# IotaWatt5_0.net
KiCad netlist of a schematic drawn in EAGLE
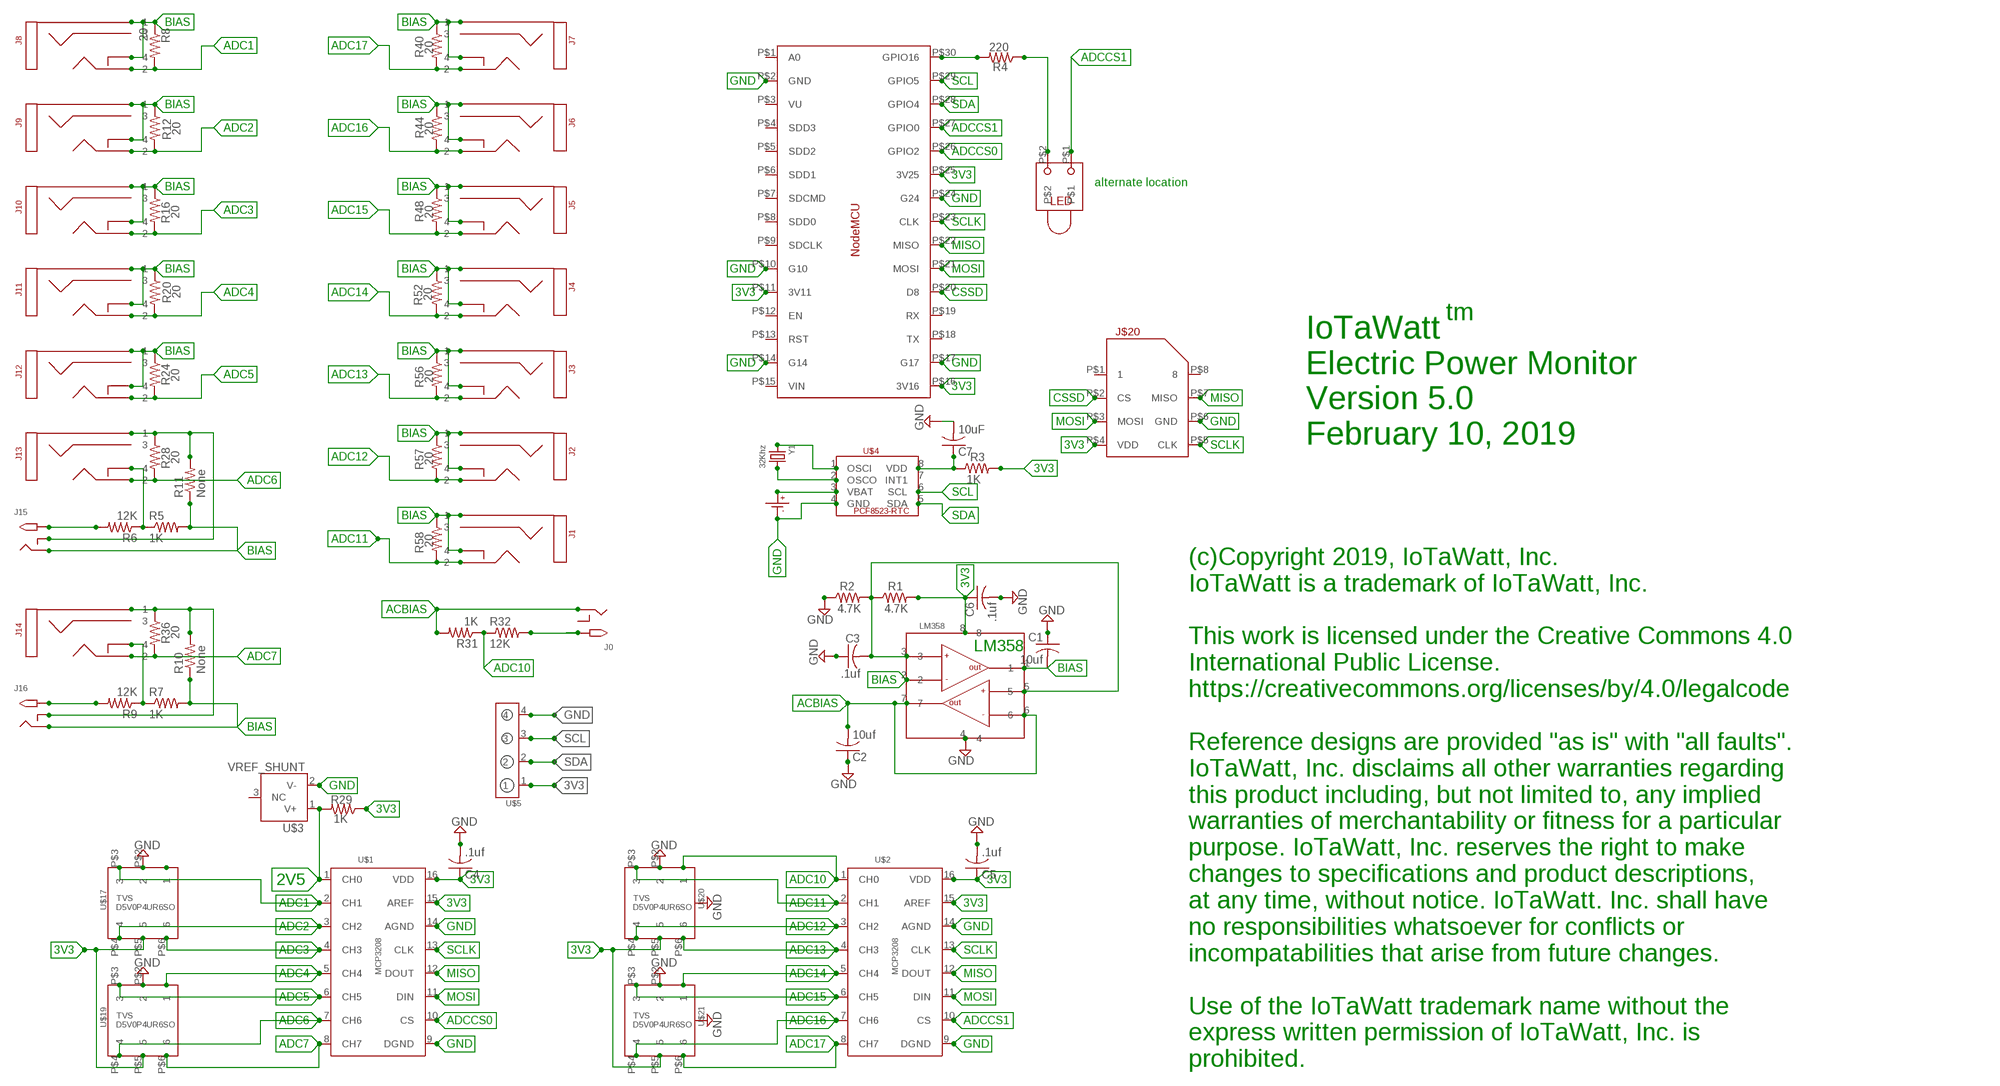
[diagram p0: schematic, sheet 1]

(export (version "E")
  (design (tool "Eeschema 10.0.6"))
  (components
    (comp (ref "C1")
      (value "10uf")
      (footprint "eagle-import:C0805")
      (fields (field (name "LCSC_PART") "C15850"))
      (libsource (lib "eagle-import") (part "C-USC0805"))
    )
    (comp (ref "C2")
      (value "10uf")
      (footprint "eagle-import:C0805")
      (fields (field (name "LCSC_PART") "C15850"))
      (libsource (lib "eagle-import") (part "C-USC0805"))
    )
    (comp (ref "C3")
      (value ".1uf")
      (footprint "eagle-import:C0805")
      (fields (field (name "LCSC_PART") "C49678"))
      (libsource (lib "eagle-import") (part "C-USC0805"))
    )
    (comp (ref "C4")
      (value ".1uf")
      (footprint "eagle-import:C0805")
      (fields (field (name "LCSC_PART") "C49678"))
      (libsource (lib "eagle-import") (part "C-USC0805"))
    )
    (comp (ref "C5")
      (value ".1uf")
      (footprint "eagle-import:C0805")
      (fields (field (name "LCSC_PART") "C49678"))
      (libsource (lib "eagle-import") (part "C-USC0805"))
    )
    (comp (ref "C6")
      (value ".1uf")
      (footprint "eagle-import:C0805")
      (fields (field (name "LCSC_PART") "C49678"))
      (libsource (lib "eagle-import") (part "C-USC0805"))
    )
    (comp (ref "C7")
      (value "10uF")
      (footprint "eagle-import:C0805")
      (fields (field (name "LCSC_PART") "C15850"))
      (libsource (lib "eagle-import") (part "C-USC0805"))
    )
    (comp (ref "J$20")
      (value "MICROSD_PUSH/PULL")
      (footprint "eagle-import:MICROSD")
      (libsource (lib "eagle-import") (part "MICROSD_PUSH/PULL"))
    )
    (comp (ref "J0")
      (value "2.1MMJACKSMT")
      (footprint "eagle-import:DCJACK_2MM_SMT")
      (libsource (lib "eagle-import") (part "2.1MMJACKSMT"))
    )
    (comp (ref "J1")
      (value "STEREO_SMD")
      (footprint "eagle-import:STEREO_SMT")
      (libsource (lib "eagle-import") (part "STEREO_SMD"))
    )
    (comp (ref "J2")
      (value "STEREO_SMD")
      (footprint "eagle-import:STEREO_SMT")
      (libsource (lib "eagle-import") (part "STEREO_SMD"))
    )
    (comp (ref "J3")
      (value "STEREO_SMD")
      (footprint "eagle-import:STEREO_SMT")
      (libsource (lib "eagle-import") (part "STEREO_SMD"))
    )
    (comp (ref "J4")
      (value "STEREO_SMD")
      (footprint "eagle-import:STEREO_SMT")
      (libsource (lib "eagle-import") (part "STEREO_SMD"))
    )
    (comp (ref "J5")
      (value "STEREO_SMD")
      (footprint "eagle-import:STEREO_SMT")
      (libsource (lib "eagle-import") (part "STEREO_SMD"))
    )
    (comp (ref "J6")
      (value "STEREO_SMD")
      (footprint "eagle-import:STEREO_SMT")
      (libsource (lib "eagle-import") (part "STEREO_SMD"))
    )
    (comp (ref "J7")
      (value "STEREO_SMD")
      (footprint "eagle-import:STEREO_SMT")
      (libsource (lib "eagle-import") (part "STEREO_SMD"))
    )
    (comp (ref "J8")
      (value "STEREO_SMD")
      (footprint "eagle-import:STEREO_SMT")
      (libsource (lib "eagle-import") (part "STEREO_SMD"))
    )
    (comp (ref "J9")
      (value "STEREO_SMD")
      (footprint "eagle-import:STEREO_SMT")
      (libsource (lib "eagle-import") (part "STEREO_SMD"))
    )
    (comp (ref "J10")
      (value "STEREO_SMD")
      (footprint "eagle-import:STEREO_SMT")
      (libsource (lib "eagle-import") (part "STEREO_SMD"))
    )
    (comp (ref "J11")
      (value "STEREO_SMD")
      (footprint "eagle-import:STEREO_SMT")
      (libsource (lib "eagle-import") (part "STEREO_SMD"))
    )
    (comp (ref "J12")
      (value "STEREO_SMD")
      (footprint "eagle-import:STEREO_SMT")
      (libsource (lib "eagle-import") (part "STEREO_SMD"))
    )
    (comp (ref "J13")
      (value "STEREO_SMD")
      (footprint "eagle-import:STEREO_SMT")
      (libsource (lib "eagle-import") (part "STEREO_SMD"))
    )
    (comp (ref "J14")
      (value "STEREO_SMD")
      (footprint "eagle-import:STEREO_SMT")
      (libsource (lib "eagle-import") (part "STEREO_SMD"))
    )
    (comp (ref "J15")
      (value "2.1MMJACKSMT")
      (footprint "eagle-import:DCJACK_2MM_SMT")
      (libsource (lib "eagle-import") (part "2.1MMJACKSMT"))
    )
    (comp (ref "J16")
      (value "2.1MMJACKSMT")
      (footprint "eagle-import:DCJACK_2MM_SMT")
      (libsource (lib "eagle-import") (part "2.1MMJACKSMT"))
    )
    (comp (ref "R1")
      (value "4.7K")
      (footprint "eagle-import:R0805")
      (fields (field (name "LCSC_PART") "C515732"))
      (libsource (lib "eagle-import") (part "R-US_R0805"))
    )
    (comp (ref "R2")
      (value "4.7K")
      (footprint "eagle-import:R0805")
      (fields (field (name "LCSC_PART") "C515732"))
      (libsource (lib "eagle-import") (part "R-US_R0805"))
    )
    (comp (ref "R3")
      (value "1K")
      (footprint "eagle-import:R0805")
      (fields (field (name "LCSC_PART") "C309081"))
      (libsource (lib "eagle-import") (part "R-US_R0805"))
    )
    (comp (ref "R4")
      (value "220")
      (footprint "eagle-import:R0805")
      (fields (field (name "LCSC_PART") "C17557"))
      (libsource (lib "eagle-import") (part "R-US_R0805"))
    )
    (comp (ref "R5")
      (value "1K")
      (footprint "eagle-import:R0805")
      (fields (field (name "LCSC_PART") "C309081"))
      (libsource (lib "eagle-import") (part "R-US_R0805"))
    )
    (comp (ref "R6")
      (value "12K")
      (footprint "eagle-import:R0805")
      (fields (field (name "LCSC_PART") "C515719"))
      (libsource (lib "eagle-import") (part "R-US_R0805"))
    )
    (comp (ref "R7")
      (value "1K")
      (footprint "eagle-import:R0805")
      (fields (field (name "LCSC_PART") "C309081"))
      (libsource (lib "eagle-import") (part "R-US_R0805"))
    )
    (comp (ref "R8")
      (value "20")
      (footprint "eagle-import:R0805")
      (fields (field (name "LCSC_PART") "C723660"))
      (libsource (lib "eagle-import") (part "R-US_R0805"))
    )
    (comp (ref "R9")
      (value "12K")
      (footprint "eagle-import:R0805")
      (fields (field (name "LCSC_PART") "C515719"))
      (libsource (lib "eagle-import") (part "R-US_R0805"))
    )
    (comp (ref "R10")
      (value "None")
      (footprint "eagle-import:R0805")
      (fields (field (name "LCSC_PART") "C17477"))
      (libsource (lib "eagle-import") (part "R-US_R0805"))
    )
    (comp (ref "R11")
      (value "None")
      (footprint "eagle-import:R0805")
      (fields (field (name "LCSC_PART") "C17477"))
      (libsource (lib "eagle-import") (part "R-US_R0805"))
    )
    (comp (ref "R12")
      (value "20")
      (footprint "eagle-import:R0805")
      (fields (field (name "LCSC_PART") "C723660"))
      (libsource (lib "eagle-import") (part "R-US_R0805"))
    )
    (comp (ref "R16")
      (value "20")
      (footprint "eagle-import:R0805")
      (fields (field (name "LCSC_PART") "C723660"))
      (libsource (lib "eagle-import") (part "R-US_R0805"))
    )
    (comp (ref "R20")
      (value "20")
      (footprint "eagle-import:R0805")
      (fields (field (name "LCSC_PART") "C723660"))
      (libsource (lib "eagle-import") (part "R-US_R0805"))
    )
    (comp (ref "R24")
      (value "20")
      (footprint "eagle-import:R0805")
      (fields (field (name "LCSC_PART") "C723660"))
      (libsource (lib "eagle-import") (part "R-US_R0805"))
    )
    (comp (ref "R28")
      (value "20")
      (footprint "eagle-import:R0805")
      (fields (field (name "LCSC_PART") "C723660"))
      (libsource (lib "eagle-import") (part "R-US_R0805"))
    )
    (comp (ref "R29")
      (value "1K")
      (footprint "eagle-import:R0805")
      (fields (field (name "LCSC_PART") "C309081"))
      (libsource (lib "eagle-import") (part "R-US_R0805"))
    )
    (comp (ref "R31")
      (value "1K")
      (footprint "eagle-import:R0805")
      (fields (field (name "LCSC_PART") "C309081"))
      (libsource (lib "eagle-import") (part "R-US_R0805"))
    )
    (comp (ref "R32")
      (value "12K")
      (footprint "eagle-import:R0805")
      (fields (field (name "LCSC_PART") "C515719"))
      (libsource (lib "eagle-import") (part "R-US_R0805"))
    )
    (comp (ref "R36")
      (value "20")
      (footprint "eagle-import:R0805")
      (fields (field (name "LCSC_PART") "C723660"))
      (libsource (lib "eagle-import") (part "R-US_R0805"))
    )
    (comp (ref "R40")
      (value "20")
      (footprint "eagle-import:R0805")
      (fields (field (name "LCSC_PART") "C723660"))
      (libsource (lib "eagle-import") (part "R-US_R0805"))
    )
    (comp (ref "R44")
      (value "20")
      (footprint "eagle-import:R0805")
      (fields (field (name "LCSC_PART") "C723660"))
      (libsource (lib "eagle-import") (part "R-US_R0805"))
    )
    (comp (ref "R48")
      (value "20")
      (footprint "eagle-import:R0805")
      (fields (field (name "LCSC_PART") "C723660"))
      (libsource (lib "eagle-import") (part "R-US_R0805"))
    )
    (comp (ref "R52")
      (value "20")
      (footprint "eagle-import:R0805")
      (fields (field (name "LCSC_PART") "C723660"))
      (libsource (lib "eagle-import") (part "R-US_R0805"))
    )
    (comp (ref "R56")
      (value "20")
      (footprint "eagle-import:R0805")
      (fields (field (name "LCSC_PART") "C723660"))
      (libsource (lib "eagle-import") (part "R-US_R0805"))
    )
    (comp (ref "R57")
      (value "20")
      (footprint "eagle-import:R0805")
      (fields (field (name "LCSC_PART") "C723660"))
      (libsource (lib "eagle-import") (part "R-US_R0805"))
    )
    (comp (ref "R58")
      (value "20")
      (footprint "eagle-import:R0805")
      (fields (field (name "LCSC_PART") "C723660"))
      (libsource (lib "eagle-import") (part "R-US_R0805"))
    )
    (comp (ref "U$1")
      (value "MCP3208")
      (footprint "eagle-import:SOIC_16")
      (fields (field (name "LCSC_PART") "C16939"))
      (libsource (lib "eagle-import") (part "MCP3208"))
    )
    (comp (ref "U$2")
      (value "MCP3208")
      (footprint "eagle-import:SOIC_16")
      (fields (field (name "LCSC_PART") "C16939"))
      (libsource (lib "eagle-import") (part "MCP3208"))
    )
    (comp (ref "U$3")
      (value "VREF_SHUNT")
      (footprint "eagle-import:SOT23_3")
      (libsource (lib "eagle-import") (part "VREF_SHUNT"))
    )
    (comp (ref "U$4")
      (value "PCF8523_RTC")
      (footprint "eagle-import:SOIC_8")
      (fields (field (name "LCSC_PART") "C2651516"))
      (libsource (lib "eagle-import") (part "PCF8523_RTC"))
    )
    (comp (ref "U$5")
      (value "HEADER_1X4")
      (footprint "eagle-import:HEADER_1X4")
      (libsource (lib "eagle-import") (part "HEADER_1X4"))
    )
    (comp (ref "U$16")
      (value "NODEMCU")
      (footprint "eagle-import:NODEMCU")
      (libsource (lib "eagle-import") (part "NODEMCU"))
    )
    (comp (ref "U$17")
      (value "TVS_4CHAN_ARRAYSC-74")
      (footprint "eagle-import:SC-74")
      (fields (field (name "LCSC_PART") "C531179"))
      (libsource (lib "eagle-import") (part "TVS_4CHAN_ARRAYSC-74"))
    )
    (comp (ref "U$18")
      (value "CR1220SMD")
      (footprint "eagle-import:CR1220SMD")
      (libsource (lib "eagle-import") (part "CR1220SMD"))
    )
    (comp (ref "U$19")
      (value "TVS_4CHAN_ARRAYSC-74")
      (footprint "eagle-import:SC-74")
      (fields (field (name "LCSC_PART") "C531179"))
      (libsource (lib "eagle-import") (part "TVS_4CHAN_ARRAYSC-74"))
    )
    (comp (ref "U$20")
      (value "TVS_4CHAN_ARRAYSC-74")
      (footprint "eagle-import:SC-74")
      (fields (field (name "LCSC_PART") "C531179"))
      (libsource (lib "eagle-import") (part "TVS_4CHAN_ARRAYSC-74"))
    )
    (comp (ref "U$21")
      (value "TVS_4CHAN_ARRAYSC-74")
      (footprint "eagle-import:SC-74")
      (fields (field (name "LCSC_PART") "C531179"))
      (libsource (lib "eagle-import") (part "TVS_4CHAN_ARRAYSC-74"))
    )
    (comp (ref "U$22")
      (value "LM358_DUAL_OP-AMP")
      (footprint "eagle-import:SOIC_8")
      (fields (field (name "LCSC_PART") "C5423"))
      (libsource (lib "eagle-import") (part "LM358_DUAL_OP-AMP"))
    )
    (comp (ref "U$23")
      (value "LED_RT_TRH")
      (footprint "eagle-import:LED_TH_RT")
      (libsource (lib "eagle-import") (part "LED_RT_TRH"))
    )
    (comp (ref "Y1")
      (value "32Khz")
      (footprint "eagle-import:CRYSTAL_8X3.8")
      (fields (field (name "LCSC_PART") "C179637"))
      (libsource (lib "eagle-import") (part "CRYSTAL8X3.8SMT"))
    )
  )
  (nets
    (net (code "1") (name "2V5") (class "Default")
      (node (ref "R29") (pin "2") (pinfunction "2_2") (pintype "passive"))
      (node (ref "U$1") (pin "1") (pinfunction "CH0_1") (pintype "input"))
      (node (ref "U$3") (pin "1") (pinfunction "V+_1") (pintype "bidirectional"))
    )
    (net (code "2") (name "3V3") (class "Default")
      (node (ref "C4") (pin "1") (pinfunction "1_1") (pintype "passive"))
      (node (ref "C5") (pin "1") (pinfunction "1_1") (pintype "passive"))
      (node (ref "C6") (pin "1") (pinfunction "1_1") (pintype "passive"))
      (node (ref "J$20") (pin "P$4") (pinfunction "VDD_P$4") (pintype "bidirectional"))
      (node (ref "R1") (pin "2") (pinfunction "2_2") (pintype "passive"))
      (node (ref "R29") (pin "1") (pinfunction "1_1") (pintype "passive"))
      (node (ref "R3") (pin "2") (pinfunction "2_2") (pintype "passive"))
      (node (ref "U$1") (pin "15") (pinfunction "AREF_15") (pintype "input"))
      (node (ref "U$1") (pin "16") (pinfunction "VDD_16") (pintype "bidirectional"))
      (node (ref "U$16") (pin "P$11") (pinfunction "3V11_P$11") (pintype "bidirectional"))
      (node (ref "U$16") (pin "P$16") (pinfunction "3V16_P$16") (pintype "bidirectional"))
      (node (ref "U$16") (pin "P$25") (pinfunction "3V25_P$25") (pintype "bidirectional"))
      (node (ref "U$17") (pin "P$5") (pinfunction "5_P$5") (pintype "bidirectional"))
      (node (ref "U$19") (pin "P$5") (pinfunction "5_P$5") (pintype "bidirectional"))
      (node (ref "U$2") (pin "15") (pinfunction "AREF_15") (pintype "input"))
      (node (ref "U$2") (pin "16") (pinfunction "VDD_16") (pintype "bidirectional"))
      (node (ref "U$20") (pin "P$5") (pinfunction "5_P$5") (pintype "bidirectional"))
      (node (ref "U$21") (pin "P$5") (pinfunction "5_P$5") (pintype "bidirectional"))
      (node (ref "U$22") (pin "8") (pinfunction "8_8") (pintype "bidirectional"))
      (node (ref "U$5") (pin "1") (pinfunction "1_1") (pintype "bidirectional"))
    )
    (net (code "3") (name "ACBIAS") (class "Default")
      (node (ref "C2") (pin "2") (pinfunction "2_2") (pintype "passive"))
      (node (ref "J0") (pin "GND") (pinfunction "RING_GND") (pintype "bidirectional"))
      (node (ref "R31") (pin "2") (pinfunction "2_2") (pintype "passive"))
      (node (ref "U$22") (pin "6") (pinfunction "6_6") (pintype "bidirectional"))
      (node (ref "U$22") (pin "7") (pinfunction "7_7") (pintype "bidirectional"))
    )
    (net (code "4") (name "ADC1") (class "Default")
      (node (ref "J8") (pin "P$2") (pinfunction "2_P$2") (pintype "bidirectional"))
      (node (ref "R8") (pin "2") (pinfunction "2_2") (pintype "passive"))
      (node (ref "U$1") (pin "2") (pinfunction "CH1_2") (pintype "input"))
      (node (ref "U$17") (pin "P$3") (pinfunction "3_P$3") (pintype "bidirectional"))
    )
    (net (code "5") (name "ADC2") (class "Default")
      (node (ref "J9") (pin "P$2") (pinfunction "2_P$2") (pintype "bidirectional"))
      (node (ref "R12") (pin "2") (pinfunction "2_2") (pintype "passive"))
      (node (ref "U$1") (pin "3") (pinfunction "CH2_3") (pintype "input"))
      (node (ref "U$17") (pin "P$4") (pinfunction "4_P$4") (pintype "bidirectional"))
    )
    (net (code "6") (name "ADC3") (class "Default")
      (node (ref "J10") (pin "P$2") (pinfunction "2_P$2") (pintype "bidirectional"))
      (node (ref "R16") (pin "2") (pinfunction "2_2") (pintype "passive"))
      (node (ref "U$1") (pin "4") (pinfunction "CH3_4") (pintype "input"))
      (node (ref "U$17") (pin "P$6") (pinfunction "6_P$6") (pintype "bidirectional"))
    )
    (net (code "7") (name "ADC4") (class "Default")
      (node (ref "J11") (pin "P$2") (pinfunction "2_P$2") (pintype "bidirectional"))
      (node (ref "R20") (pin "2") (pinfunction "2_2") (pintype "passive"))
      (node (ref "U$1") (pin "5") (pinfunction "CH4_5") (pintype "bidirectional"))
      (node (ref "U$19") (pin "P$1") (pinfunction "1_P$1") (pintype "bidirectional"))
    )
    (net (code "8") (name "ADC5") (class "Default")
      (node (ref "J12") (pin "P$2") (pinfunction "2_P$2") (pintype "bidirectional"))
      (node (ref "R24") (pin "2") (pinfunction "2_2") (pintype "passive"))
      (node (ref "U$1") (pin "6") (pinfunction "CH5_6") (pintype "bidirectional"))
      (node (ref "U$19") (pin "P$3") (pinfunction "3_P$3") (pintype "bidirectional"))
    )
    (net (code "9") (name "ADC6") (class "Default")
      (node (ref "J13") (pin "P$2") (pinfunction "2_P$2") (pintype "bidirectional"))
      (node (ref "R28") (pin "2") (pinfunction "2_2") (pintype "passive"))
      (node (ref "U$1") (pin "7") (pinfunction "CH6_7") (pintype "input"))
      (node (ref "U$19") (pin "P$4") (pinfunction "4_P$4") (pintype "bidirectional"))
    )
    (net (code "10") (name "ADC7") (class "Default")
      (node (ref "J14") (pin "P$2") (pinfunction "2_P$2") (pintype "bidirectional"))
      (node (ref "R36") (pin "2") (pinfunction "2_2") (pintype "passive"))
      (node (ref "U$1") (pin "8") (pinfunction "CH7_8") (pintype "bidirectional"))
      (node (ref "U$19") (pin "P$6") (pinfunction "6_P$6") (pintype "bidirectional"))
    )
    (net (code "11") (name "ADC10") (class "Default")
      (node (ref "R31") (pin "1") (pinfunction "1_1") (pintype "passive"))
      (node (ref "R32") (pin "1") (pinfunction "1_1") (pintype "passive"))
      (node (ref "U$2") (pin "1") (pinfunction "CH0_1") (pintype "input"))
      (node (ref "U$20") (pin "P$1") (pinfunction "1_P$1") (pintype "bidirectional"))
    )
    (net (code "12") (name "ADC11") (class "Default")
      (node (ref "J1") (pin "P$2") (pinfunction "2_P$2") (pintype "bidirectional"))
      (node (ref "R58") (pin "2") (pinfunction "2_2") (pintype "passive"))
      (node (ref "U$2") (pin "2") (pinfunction "CH1_2") (pintype "input"))
      (node (ref "U$20") (pin "P$3") (pinfunction "3_P$3") (pintype "bidirectional"))
    )
    (net (code "13") (name "ADC12") (class "Default")
      (node (ref "J2") (pin "P$2") (pinfunction "2_P$2") (pintype "bidirectional"))
      (node (ref "R57") (pin "2") (pinfunction "2_2") (pintype "passive"))
      (node (ref "U$2") (pin "3") (pinfunction "CH2_3") (pintype "input"))
      (node (ref "U$20") (pin "P$4") (pinfunction "4_P$4") (pintype "bidirectional"))
    )
    (net (code "14") (name "ADC13") (class "Default")
      (node (ref "J3") (pin "P$2") (pinfunction "2_P$2") (pintype "bidirectional"))
      (node (ref "R56") (pin "2") (pinfunction "2_2") (pintype "passive"))
      (node (ref "U$2") (pin "4") (pinfunction "CH3_4") (pintype "input"))
      (node (ref "U$20") (pin "P$6") (pinfunction "6_P$6") (pintype "bidirectional"))
    )
    (net (code "15") (name "ADC14") (class "Default")
      (node (ref "J4") (pin "P$2") (pinfunction "2_P$2") (pintype "bidirectional"))
      (node (ref "R52") (pin "2") (pinfunction "2_2") (pintype "passive"))
      (node (ref "U$2") (pin "5") (pinfunction "CH4_5") (pintype "bidirectional"))
      (node (ref "U$21") (pin "P$1") (pinfunction "1_P$1") (pintype "bidirectional"))
    )
    (net (code "16") (name "ADC15") (class "Default")
      (node (ref "J5") (pin "P$2") (pinfunction "2_P$2") (pintype "bidirectional"))
      (node (ref "R48") (pin "2") (pinfunction "2_2") (pintype "passive"))
      (node (ref "U$2") (pin "6") (pinfunction "CH5_6") (pintype "bidirectional"))
      (node (ref "U$21") (pin "P$3") (pinfunction "3_P$3") (pintype "bidirectional"))
    )
    (net (code "17") (name "ADC16") (class "Default")
      (node (ref "J6") (pin "P$2") (pinfunction "2_P$2") (pintype "bidirectional"))
      (node (ref "R44") (pin "2") (pinfunction "2_2") (pintype "passive"))
      (node (ref "U$2") (pin "7") (pinfunction "CH6_7") (pintype "input"))
      (node (ref "U$21") (pin "P$4") (pinfunction "4_P$4") (pintype "bidirectional"))
    )
    (net (code "18") (name "ADC17") (class "Default")
      (node (ref "J7") (pin "P$2") (pinfunction "2_P$2") (pintype "bidirectional"))
      (node (ref "R40") (pin "2") (pinfunction "2_2") (pintype "passive"))
      (node (ref "U$2") (pin "8") (pinfunction "CH7_8") (pintype "bidirectional"))
      (node (ref "U$21") (pin "P$6") (pinfunction "6_P$6") (pintype "bidirectional"))
    )
    (net (code "19") (name "ADCCS0") (class "Default")
      (node (ref "U$1") (pin "10") (pinfunction "CS_10") (pintype "input"))
      (node (ref "U$16") (pin "P$26") (pinfunction "GPIO2_P$26") (pintype "bidirectional"))
    )
    (net (code "20") (name "ADCCS1") (class "Default")
      (node (ref "U$16") (pin "P$27") (pinfunction "GPIO0_P$27") (pintype "bidirectional"))
      (node (ref "U$2") (pin "10") (pinfunction "CS_10") (pintype "input"))
      (node (ref "U$23") (pin "P$1") (pinfunction "P$1_P$1") (pintype "bidirectional"))
    )
    (net (code "21") (name "BIAS") (class "Default")
      (node (ref "C1") (pin "2") (pinfunction "2_2") (pintype "passive"))
      (node (ref "J1") (pin "P$1") (pinfunction "1_P$1") (pintype "bidirectional"))
      (node (ref "J1") (pin "P$4") (pinfunction "4_P$4") (pintype "bidirectional"))
      (node (ref "J10") (pin "P$1") (pinfunction "1_P$1") (pintype "bidirectional"))
      (node (ref "J10") (pin "P$4") (pinfunction "4_P$4") (pintype "bidirectional"))
      (node (ref "J11") (pin "P$1") (pinfunction "1_P$1") (pintype "bidirectional"))
      (node (ref "J11") (pin "P$4") (pinfunction "4_P$4") (pintype "bidirectional"))
      (node (ref "J12") (pin "P$1") (pinfunction "1_P$1") (pintype "bidirectional"))
      (node (ref "J12") (pin "P$4") (pinfunction "4_P$4") (pintype "bidirectional"))
      (node (ref "J15") (pin "GND") (pinfunction "RING_GND") (pintype "bidirectional"))
      (node (ref "J16") (pin "GND") (pinfunction "RING_GND") (pintype "bidirectional"))
      (node (ref "J2") (pin "P$1") (pinfunction "1_P$1") (pintype "bidirectional"))
      (node (ref "J2") (pin "P$4") (pinfunction "4_P$4") (pintype "bidirectional"))
      (node (ref "J3") (pin "P$1") (pinfunction "1_P$1") (pintype "bidirectional"))
      (node (ref "J3") (pin "P$4") (pinfunction "4_P$4") (pintype "bidirectional"))
      (node (ref "J4") (pin "P$1") (pinfunction "1_P$1") (pintype "bidirectional"))
      (node (ref "J4") (pin "P$4") (pinfunction "4_P$4") (pintype "bidirectional"))
      (node (ref "J5") (pin "P$1") (pinfunction "1_P$1") (pintype "bidirectional"))
      (node (ref "J5") (pin "P$4") (pinfunction "4_P$4") (pintype "bidirectional"))
      (node (ref "J6") (pin "P$1") (pinfunction "1_P$1") (pintype "bidirectional"))
      (node (ref "J6") (pin "P$4") (pinfunction "4_P$4") (pintype "bidirectional"))
      (node (ref "J7") (pin "P$1") (pinfunction "1_P$1") (pintype "bidirectional"))
      (node (ref "J7") (pin "P$4") (pinfunction "4_P$4") (pintype "bidirectional"))
      (node (ref "J8") (pin "P$1") (pinfunction "1_P$1") (pintype "bidirectional"))
      (node (ref "J8") (pin "P$4") (pinfunction "4_P$4") (pintype "bidirectional"))
      (node (ref "J9") (pin "P$1") (pinfunction "1_P$1") (pintype "bidirectional"))
      (node (ref "J9") (pin "P$4") (pinfunction "4_P$4") (pintype "bidirectional"))
      (node (ref "R10") (pin "1") (pinfunction "1_1") (pintype "passive"))
      (node (ref "R11") (pin "1") (pinfunction "1_1") (pintype "passive"))
      (node (ref "R12") (pin "1") (pinfunction "1_1") (pintype "passive"))
      (node (ref "R16") (pin "1") (pinfunction "1_1") (pintype "passive"))
      (node (ref "R20") (pin "1") (pinfunction "1_1") (pintype "passive"))
      (node (ref "R24") (pin "1") (pinfunction "1_1") (pintype "passive"))
      (node (ref "R40") (pin "1") (pinfunction "1_1") (pintype "passive"))
      (node (ref "R44") (pin "1") (pinfunction "1_1") (pintype "passive"))
      (node (ref "R48") (pin "1") (pinfunction "1_1") (pintype "passive"))
      (node (ref "R5") (pin "2") (pinfunction "2_2") (pintype "passive"))
      (node (ref "R52") (pin "1") (pinfunction "1_1") (pintype "passive"))
      (node (ref "R56") (pin "1") (pinfunction "1_1") (pintype "passive"))
      (node (ref "R57") (pin "1") (pinfunction "1_1") (pintype "passive"))
      (node (ref "R58") (pin "1") (pinfunction "1_1") (pintype "passive"))
      (node (ref "R7") (pin "2") (pinfunction "2_2") (pintype "passive"))
      (node (ref "R8") (pin "1") (pinfunction "1_1") (pintype "passive"))
      (node (ref "U$22") (pin "1") (pinfunction "1_1") (pintype "bidirectional"))
      (node (ref "U$22") (pin "2") (pinfunction "2_2") (pintype "bidirectional"))
    )
    (net (code "22") (name "CSSD") (class "Default")
      (node (ref "J$20") (pin "P$2") (pinfunction "CS_P$2") (pintype "bidirectional"))
      (node (ref "U$16") (pin "P$20") (pinfunction "D8_P$20") (pintype "bidirectional"))
    )
    (net (code "23") (name "GND") (class "Default")
      (node (ref "C1") (pin "1") (pinfunction "1_1") (pintype "passive"))
      (node (ref "C2") (pin "1") (pinfunction "1_1") (pintype "passive"))
      (node (ref "C3") (pin "1") (pinfunction "1_1") (pintype "passive"))
      (node (ref "C4") (pin "2") (pinfunction "2_2") (pintype "passive"))
      (node (ref "C5") (pin "2") (pinfunction "2_2") (pintype "passive"))
      (node (ref "C6") (pin "2") (pinfunction "2_2") (pintype "passive"))
      (node (ref "C7") (pin "2") (pinfunction "2_2") (pintype "passive"))
      (node (ref "J$20") (pin "P$6") (pinfunction "GND_P$6") (pintype "bidirectional"))
      (node (ref "R2") (pin "1") (pinfunction "1_1") (pintype "passive"))
      (node (ref "U$1") (pin "14") (pinfunction "AGND_14") (pintype "input"))
      (node (ref "U$1") (pin "9") (pinfunction "DGND_9") (pintype "bidirectional"))
      (node (ref "U$16") (pin "P$10") (pinfunction "G10_P$10") (pintype "bidirectional"))
      (node (ref "U$16") (pin "P$14") (pinfunction "G14_P$14") (pintype "bidirectional"))
      (node (ref "U$16") (pin "P$17") (pinfunction "G17_P$17") (pintype "bidirectional"))
      (node (ref "U$16") (pin "P$2") (pinfunction "GND_P$2") (pintype "bidirectional"))
      (node (ref "U$16") (pin "P$24") (pinfunction "G24_P$24") (pintype "bidirectional"))
      (node (ref "U$17") (pin "P$2") (pinfunction "2_P$2") (pintype "bidirectional"))
      (node (ref "U$18") (pin "P-") (pinfunction "P$-_P-") (pintype "bidirectional"))
      (node (ref "U$19") (pin "P$2") (pinfunction "2_P$2") (pintype "bidirectional"))
      (node (ref "U$2") (pin "14") (pinfunction "AGND_14") (pintype "input"))
      (node (ref "U$2") (pin "9") (pinfunction "DGND_9") (pintype "bidirectional"))
      (node (ref "U$20") (pin "P$2") (pinfunction "2_P$2") (pintype "bidirectional"))
      (node (ref "U$21") (pin "P$2") (pinfunction "2_P$2") (pintype "bidirectional"))
      (node (ref "U$22") (pin "4") (pinfunction "4_4") (pintype "bidirectional"))
      (node (ref "U$3") (pin "2") (pinfunction "V-_2") (pintype "bidirectional"))
      (node (ref "U$4") (pin "4") (pinfunction "GND_4") (pintype "bidirectional"))
      (node (ref "U$5") (pin "4") (pinfunction "4_4") (pintype "bidirectional"))
    )
    (net (code "24") (name "MISO") (class "Default")
      (node (ref "J$20") (pin "P$7") (pinfunction "MISO_P$7") (pintype "bidirectional"))
      (node (ref "U$1") (pin "12") (pinfunction "DOUT_12") (pintype "bidirectional"))
      (node (ref "U$16") (pin "P$22") (pinfunction "MISO_P$22") (pintype "bidirectional"))
      (node (ref "U$2") (pin "12") (pinfunction "DOUT_12") (pintype "bidirectional"))
    )
    (net (code "25") (name "MOSI") (class "Default")
      (node (ref "J$20") (pin "P$3") (pinfunction "MOSI_P$3") (pintype "bidirectional"))
      (node (ref "U$1") (pin "11") (pinfunction "DIN_11") (pintype "input"))
      (node (ref "U$16") (pin "P$21") (pinfunction "MOSI_P$21") (pintype "bidirectional"))
      (node (ref "U$2") (pin "11") (pinfunction "DIN_11") (pintype "input"))
    )
    (net (code "26") (name "Net-(C3-Pad2)") (class "Default")
      (node (ref "C3") (pin "2") (pinfunction "2_2") (pintype "passive"))
      (node (ref "R1") (pin "1") (pinfunction "1_1") (pintype "passive"))
      (node (ref "R2") (pin "2") (pinfunction "2_2") (pintype "passive"))
      (node (ref "U$22") (pin "3") (pinfunction "3_3") (pintype "bidirectional"))
      (node (ref "U$22") (pin "5") (pinfunction "5_5") (pintype "bidirectional"))
    )
    (net (code "27") (name "Net-(J0-TIP)") (class "Default")
      (node (ref "J0") (pin "PWR2") (pinfunction "TIP_PWR2") (pintype "bidirectional"))
      (node (ref "R32") (pin "2") (pinfunction "2_2") (pintype "passive"))
    )
    (net (code "28") (name "Net-(J13-1)") (class "Default")
      (node (ref "J13") (pin "P$1") (pinfunction "1_P$1") (pintype "bidirectional"))
      (node (ref "J15") (pin "GNDBREAK") (pinfunction "RING_SW_GNDBREAK") (pintype "bidirectional"))
      (node (ref "R11") (pin "2") (pinfunction "2_2") (pintype "passive"))
      (node (ref "R28") (pin "1") (pinfunction "1_1") (pintype "passive"))
    )
    (net (code "29") (name "Net-(J13-4)") (class "Default")
      (node (ref "J13") (pin "P$4") (pinfunction "4_P$4") (pintype "bidirectional"))
      (node (ref "R5") (pin "1") (pinfunction "1_1") (pintype "passive"))
      (node (ref "R6") (pin "1") (pinfunction "1_1") (pintype "passive"))
    )
    (net (code "30") (name "Net-(J14-1)") (class "Default")
      (node (ref "J14") (pin "P$1") (pinfunction "1_P$1") (pintype "bidirectional"))
      (node (ref "J16") (pin "GNDBREAK") (pinfunction "RING_SW_GNDBREAK") (pintype "bidirectional"))
      (node (ref "R10") (pin "2") (pinfunction "2_2") (pintype "passive"))
      (node (ref "R36") (pin "1") (pinfunction "1_1") (pintype "passive"))
    )
    (net (code "31") (name "Net-(J14-4)") (class "Default")
      (node (ref "J14") (pin "P$4") (pinfunction "4_P$4") (pintype "bidirectional"))
      (node (ref "R7") (pin "1") (pinfunction "1_1") (pintype "passive"))
      (node (ref "R9") (pin "1") (pinfunction "1_1") (pintype "passive"))
    )
    (net (code "32") (name "Net-(J15-TIP)") (class "Default")
      (node (ref "J15") (pin "PWR2") (pinfunction "TIP_PWR2") (pintype "bidirectional"))
      (node (ref "R6") (pin "2") (pinfunction "2_2") (pintype "passive"))
    )
    (net (code "33") (name "Net-(J16-TIP)") (class "Default")
      (node (ref "J16") (pin "PWR2") (pinfunction "TIP_PWR2") (pintype "bidirectional"))
      (node (ref "R9") (pin "2") (pinfunction "2_2") (pintype "passive"))
    )
    (net (code "34") (name "Net-(R4-Pad1)") (class "Default")
      (node (ref "R4") (pin "1") (pinfunction "1_1") (pintype "passive"))
      (node (ref "U$23") (pin "P$2") (pinfunction "P$2_P$2") (pintype "bidirectional"))
    )
    (net (code "35") (name "Net-(U$4-OSCI)") (class "Default")
      (node (ref "U$4") (pin "1") (pinfunction "OSCI_1") (pintype "bidirectional"))
      (node (ref "Y1") (pin "P$1") (pinfunction "1_P$1") (pintype "passive"))
    )
    (net (code "36") (name "Net-(U$4-OSCO)") (class "Default")
      (node (ref "U$4") (pin "2") (pinfunction "OSCO_2") (pintype "bidirectional"))
      (node (ref "Y1") (pin "P$4") (pinfunction "2_P$4") (pintype "passive"))
    )
    (net (code "37") (name "Net-(U$4-VDD)") (class "Default")
      (node (ref "C7") (pin "1") (pinfunction "1_1") (pintype "passive"))
      (node (ref "R3") (pin "1") (pinfunction "1_1") (pintype "passive"))
      (node (ref "U$4") (pin "8") (pinfunction "VDD_8") (pintype "bidirectional"))
    )
    (net (code "38") (name "Net-(U$16-GPIO16)") (class "Default")
      (node (ref "R4") (pin "2") (pinfunction "2_2") (pintype "passive"))
      (node (ref "U$16") (pin "P$30") (pinfunction "GPIO16_P$30") (pintype "bidirectional"))
    )
    (net (code "39") (name "Net-(U$18-P$+)") (class "Default")
      (node (ref "U$18") (pin "P+") (pinfunction "P$+_P+") (pintype "bidirectional"))
      (node (ref "U$4") (pin "3") (pinfunction "VBAT_3") (pintype "bidirectional"))
    )
    (net (code "40") (name "SCL") (class "Default")
      (node (ref "U$16") (pin "P$29") (pinfunction "GPIO5_P$29") (pintype "bidirectional"))
      (node (ref "U$4") (pin "6") (pinfunction "SCL_6") (pintype "bidirectional"))
      (node (ref "U$5") (pin "3") (pinfunction "3_3") (pintype "bidirectional"))
    )
    (net (code "41") (name "SCLK") (class "Default")
      (node (ref "J$20") (pin "P$5") (pinfunction "CLK_P$5") (pintype "bidirectional"))
      (node (ref "U$1") (pin "13") (pinfunction "CLK_13") (pintype "input"))
      (node (ref "U$16") (pin "P$23") (pinfunction "CLK_P$23") (pintype "bidirectional"))
      (node (ref "U$2") (pin "13") (pinfunction "CLK_13") (pintype "input"))
    )
    (net (code "42") (name "SDA") (class "Default")
      (node (ref "U$16") (pin "P$28") (pinfunction "GPIO4_P$28") (pintype "bidirectional"))
      (node (ref "U$4") (pin "5") (pinfunction "SDA_5") (pintype "bidirectional"))
      (node (ref "U$5") (pin "2") (pinfunction "2_2") (pintype "bidirectional"))
    )
    (net (code "43") (name "unconnected-(J$20-1-PadP$1)") (class "Default")
      (node (ref "J$20") (pin "P$1") (pinfunction "1_P$1") (pintype "bidirectional"))
    )
    (net (code "44") (name "unconnected-(J$20-8-PadP$8)") (class "Default")
      (node (ref "J$20") (pin "P$8") (pinfunction "8_P$8") (pintype "bidirectional"))
    )
    (net (code "45") (name "unconnected-(J0-RING_SW-PadGNDBREAK)") (class "Default")
      (node (ref "J0") (pin "GNDBREAK") (pinfunction "RING_SW_GNDBREAK") (pintype "bidirectional"))
    )
    (net (code "46") (name "unconnected-(J1-3-PadP$3)") (class "Default")
      (node (ref "J1") (pin "P$3") (pinfunction "3_P$3") (pintype "bidirectional"))
    )
    (net (code "47") (name "unconnected-(J2-3-PadP$3)") (class "Default")
      (node (ref "J2") (pin "P$3") (pinfunction "3_P$3") (pintype "bidirectional"))
    )
    (net (code "48") (name "unconnected-(J3-3-PadP$3)") (class "Default")
      (node (ref "J3") (pin "P$3") (pinfunction "3_P$3") (pintype "bidirectional"))
    )
    (net (code "49") (name "unconnected-(J4-3-PadP$3)") (class "Default")
      (node (ref "J4") (pin "P$3") (pinfunction "3_P$3") (pintype "bidirectional"))
    )
    (net (code "50") (name "unconnected-(J5-3-PadP$3)") (class "Default")
      (node (ref "J5") (pin "P$3") (pinfunction "3_P$3") (pintype "bidirectional"))
    )
    (net (code "51") (name "unconnected-(J6-3-PadP$3)") (class "Default")
      (node (ref "J6") (pin "P$3") (pinfunction "3_P$3") (pintype "bidirectional"))
    )
    (net (code "52") (name "unconnected-(J7-3-PadP$3)") (class "Default")
      (node (ref "J7") (pin "P$3") (pinfunction "3_P$3") (pintype "bidirectional"))
    )
    (net (code "53") (name "unconnected-(J8-3-PadP$3)") (class "Default")
      (node (ref "J8") (pin "P$3") (pinfunction "3_P$3") (pintype "bidirectional"))
    )
    (net (code "54") (name "unconnected-(J9-3-PadP$3)") (class "Default")
      (node (ref "J9") (pin "P$3") (pinfunction "3_P$3") (pintype "bidirectional"))
    )
    (net (code "55") (name "unconnected-(J10-3-PadP$3)") (class "Default")
      (node (ref "J10") (pin "P$3") (pinfunction "3_P$3") (pintype "bidirectional"))
    )
    (net (code "56") (name "unconnected-(J11-3-PadP$3)") (class "Default")
      (node (ref "J11") (pin "P$3") (pinfunction "3_P$3") (pintype "bidirectional"))
    )
    (net (code "57") (name "unconnected-(J12-3-PadP$3)") (class "Default")
      (node (ref "J12") (pin "P$3") (pinfunction "3_P$3") (pintype "bidirectional"))
    )
    (net (code "58") (name "unconnected-(J13-3-PadP$3)") (class "Default")
      (node (ref "J13") (pin "P$3") (pinfunction "3_P$3") (pintype "bidirectional"))
    )
    (net (code "59") (name "unconnected-(J14-3-PadP$3)") (class "Default")
      (node (ref "J14") (pin "P$3") (pinfunction "3_P$3") (pintype "bidirectional"))
    )
    (net (code "60") (name "unconnected-(U$3-NC-Pad3)") (class "Default")
      (node (ref "U$3") (pin "3") (pinfunction "NC_3") (pintype "bidirectional"))
    )
    (net (code "61") (name "unconnected-(U$4-INT1-Pad7)") (class "Default")
      (node (ref "U$4") (pin "7") (pinfunction "INT1_7") (pintype "bidirectional"))
    )
    (net (code "62") (name "unconnected-(U$16-A0-PadP$1)") (class "Default")
      (node (ref "U$16") (pin "P$1") (pinfunction "A0_P$1") (pintype "bidirectional"))
    )
    (net (code "63") (name "unconnected-(U$16-EN-PadP$12)") (class "Default")
      (node (ref "U$16") (pin "P$12") (pinfunction "EN_P$12") (pintype "bidirectional"))
    )
    (net (code "64") (name "unconnected-(U$16-RST-PadP$13)") (class "Default")
      (node (ref "U$16") (pin "P$13") (pinfunction "RST_P$13") (pintype "bidirectional"))
    )
    (net (code "65") (name "unconnected-(U$16-RX-PadP$19)") (class "Default")
      (node (ref "U$16") (pin "P$19") (pinfunction "RX_P$19") (pintype "bidirectional"))
    )
    (net (code "66") (name "unconnected-(U$16-SDCLK-PadP$9)") (class "Default")
      (node (ref "U$16") (pin "P$9") (pinfunction "SDCLK_P$9") (pintype "bidirectional"))
    )
    (net (code "67") (name "unconnected-(U$16-SDCMD-PadP$7)") (class "Default")
      (node (ref "U$16") (pin "P$7") (pinfunction "SDCMD_P$7") (pintype "bidirectional"))
    )
    (net (code "68") (name "unconnected-(U$16-SDD0-PadP$8)") (class "Default")
      (node (ref "U$16") (pin "P$8") (pinfunction "SDD0_P$8") (pintype "bidirectional"))
    )
    (net (code "69") (name "unconnected-(U$16-SDD1-PadP$6)") (class "Default")
      (node (ref "U$16") (pin "P$6") (pinfunction "SDD1_P$6") (pintype "bidirectional"))
    )
    (net (code "70") (name "unconnected-(U$16-SDD2-PadP$5)") (class "Default")
      (node (ref "U$16") (pin "P$5") (pinfunction "SDD2_P$5") (pintype "bidirectional"))
    )
    (net (code "71") (name "unconnected-(U$16-SDD3-PadP$4)") (class "Default")
      (node (ref "U$16") (pin "P$4") (pinfunction "SDD3_P$4") (pintype "bidirectional"))
    )
    (net (code "72") (name "unconnected-(U$16-TX-PadP$18)") (class "Default")
      (node (ref "U$16") (pin "P$18") (pinfunction "TX_P$18") (pintype "bidirectional"))
    )
    (net (code "73") (name "unconnected-(U$16-VIN-PadP$15)") (class "Default")
      (node (ref "U$16") (pin "P$15") (pinfunction "VIN_P$15") (pintype "bidirectional"))
    )
    (net (code "74") (name "unconnected-(U$16-VU-PadP$3)") (class "Default")
      (node (ref "U$16") (pin "P$3") (pinfunction "VU_P$3") (pintype "bidirectional"))
    )
    (net (code "75") (name "unconnected-(U$17-1-PadP$1)") (class "Default")
      (node (ref "U$17") (pin "P$1") (pinfunction "1_P$1") (pintype "bidirectional"))
    )
  )
)
